# foot-board.net
KiCad netlist of a schematic drawn in EAGLE
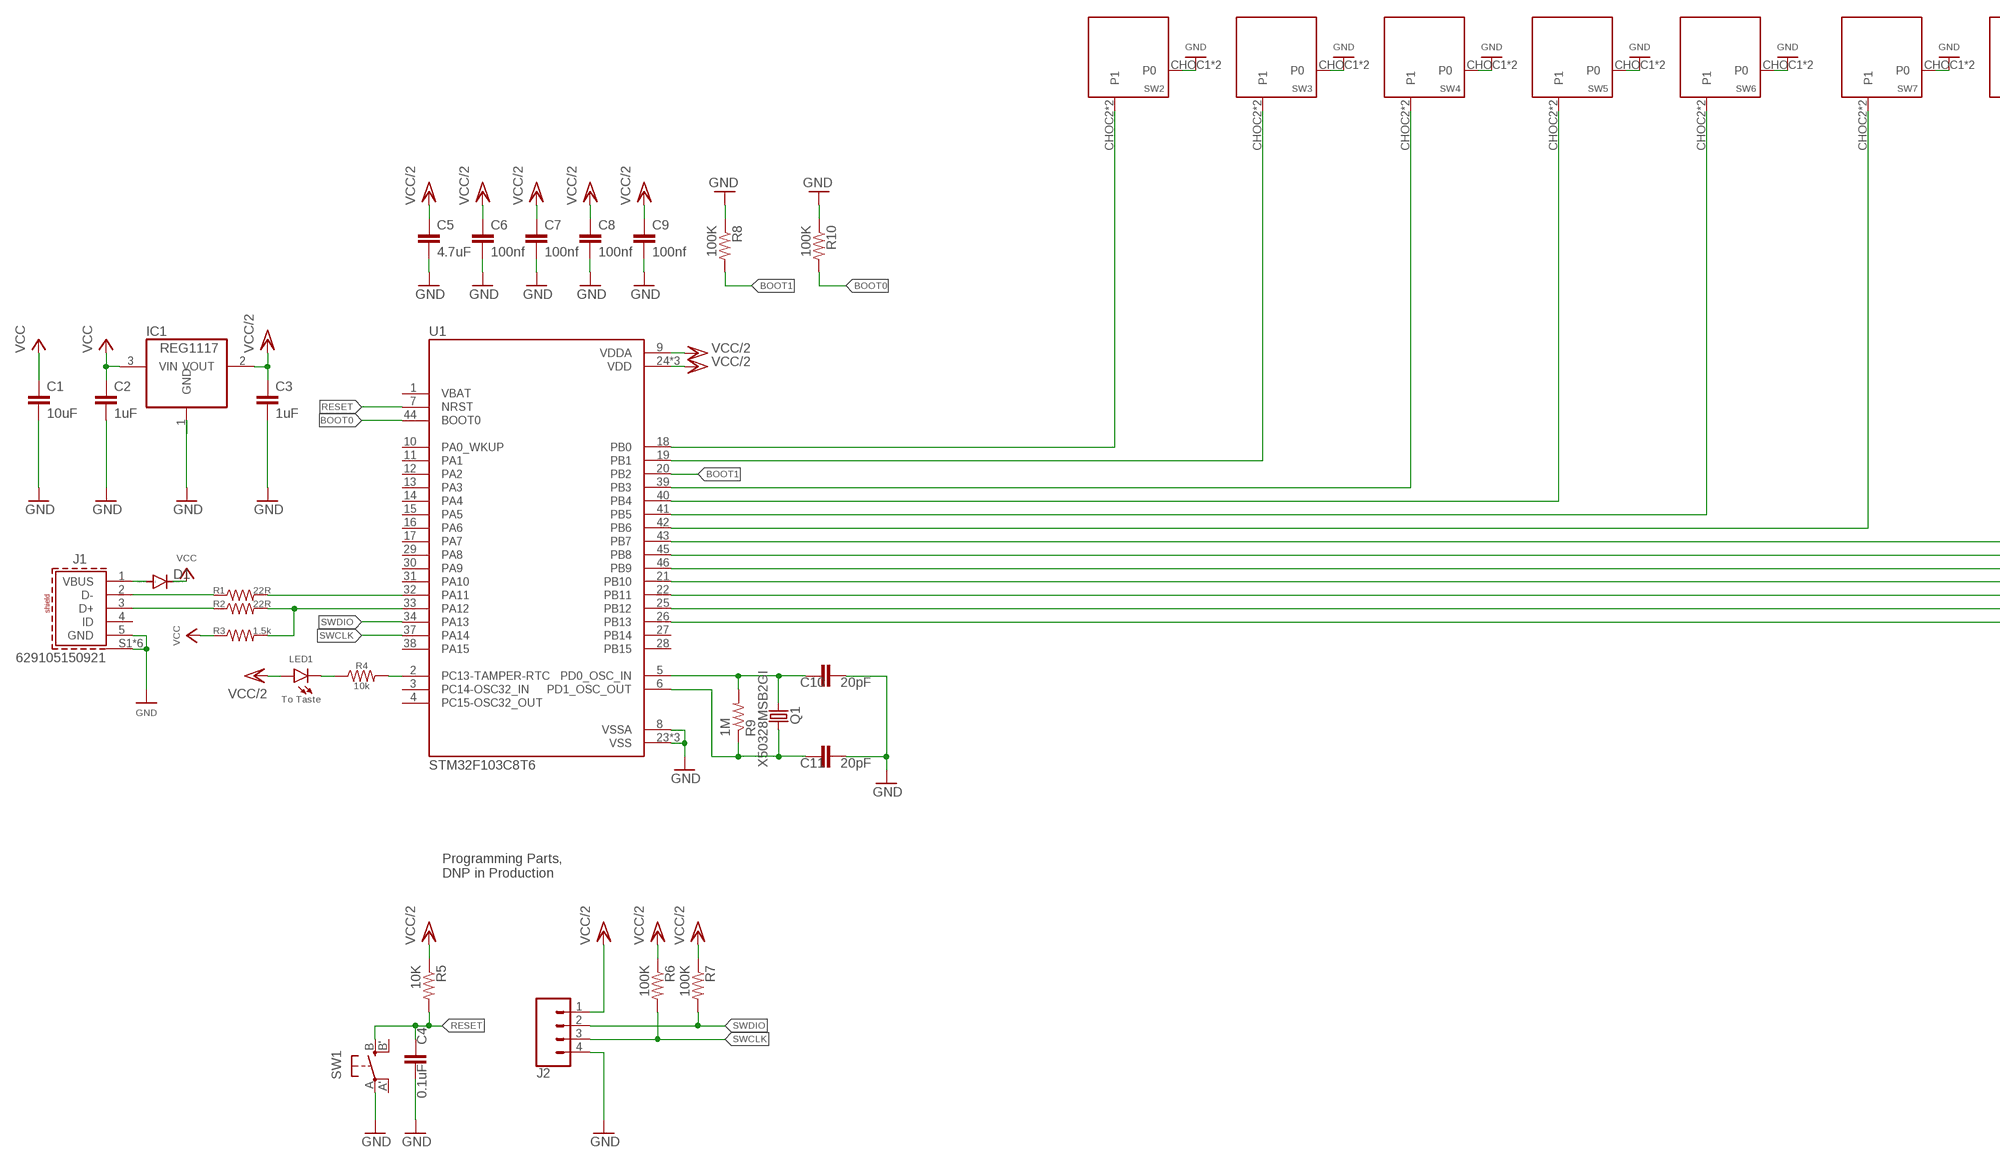
[diagram p0: schematic, sheet 1, part 1 of 2]
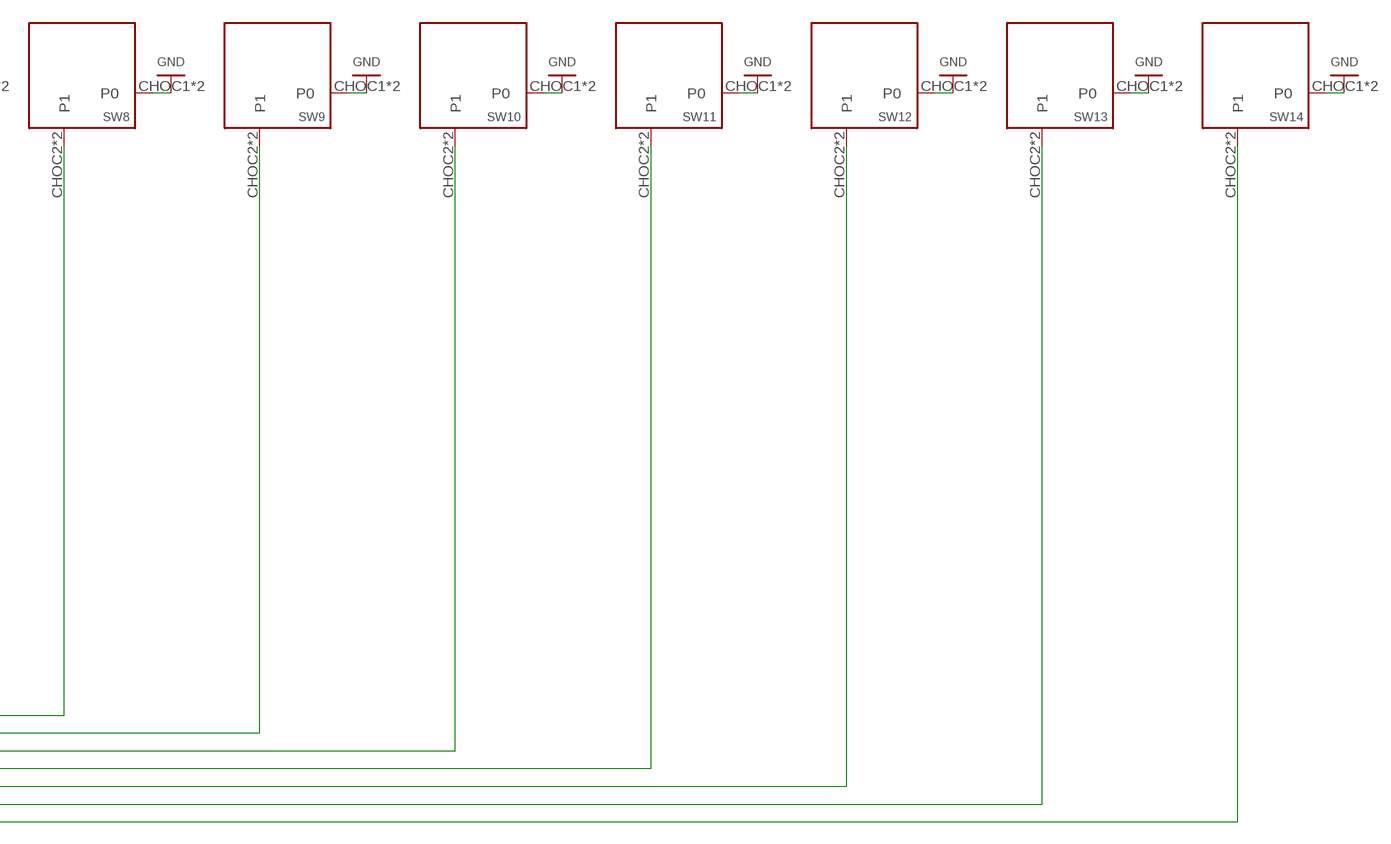
[diagram p1: schematic, sheet 1, part 2 of 2]

(export (version "E")
  (design (tool "Eeschema 10.0.6"))
  (components
    (comp (ref "C1")
      (value "10uF")
      (footprint "eagle-import:C0805")
      (libsource (lib "eagle-import") (part "C-EUC0805"))
    )
    (comp (ref "C2")
      (value "1uF")
      (footprint "eagle-import:C0402")
      (libsource (lib "eagle-import") (part "C-EUC0402"))
    )
    (comp (ref "C3")
      (value "1uF")
      (footprint "eagle-import:C0402")
      (libsource (lib "eagle-import") (part "C-EUC0402"))
    )
    (comp (ref "C4")
      (value "0.1uF")
      (footprint "eagle-import:C0402")
      (libsource (lib "eagle-import") (part "C-EUC0402"))
    )
    (comp (ref "C5")
      (value "4.7uF")
      (footprint "eagle-import:C0805")
      (libsource (lib "eagle-import") (part "C-EUC0805"))
    )
    (comp (ref "C6")
      (value "100nf")
      (footprint "eagle-import:C0402")
      (libsource (lib "eagle-import") (part "C-EUC0402"))
    )
    (comp (ref "C7")
      (value "100nf")
      (footprint "eagle-import:C0402")
      (libsource (lib "eagle-import") (part "C-EUC0402"))
    )
    (comp (ref "C8")
      (value "100nf")
      (footprint "eagle-import:C0402")
      (libsource (lib "eagle-import") (part "C-EUC0402"))
    )
    (comp (ref "C9")
      (value "100nf")
      (footprint "eagle-import:C0402")
      (libsource (lib "eagle-import") (part "C-EUC0402"))
    )
    (comp (ref "C10")
      (value "20pF")
      (footprint "eagle-import:C0402")
      (libsource (lib "eagle-import") (part "C-EUC0402"))
    )
    (comp (ref "C11")
      (value "20pF")
      (footprint "eagle-import:C0402")
      (libsource (lib "eagle-import") (part "C-EUC0402"))
    )
    (comp (ref "D1")
      (value "DIODE-DO214AC")
      (footprint "eagle-import:DO214AC")
      (libsource (lib "eagle-import") (part "DIODE-DO214AC"))
    )
    (comp (ref "IC1")
      (value "REG1117")
      (footprint "eagle-import:SOT223")
      (libsource (lib "eagle-import") (part "REG1117"))
    )
    (comp (ref "J1")
      (value "629105150921")
      (footprint "eagle-import:629105150921")
      (libsource (lib "eagle-import") (part "629105150921"))
    )
    (comp (ref "J2")
      (value "CONN_04")
      (footprint "eagle-import:1X04")
      (libsource (lib "eagle-import") (part "CONN_04"))
    )
    (comp (ref "LED1")
      (value "To Taste")
      (footprint "eagle-import:CHIPLED_0603")
      (libsource (lib "eagle-import") (part "LEDCHIPLED_0603"))
    )
    (comp (ref "Q1")
      (value "X50328MSB2GI")
      (footprint "eagle-import:6.0X3.5_2")
      (libsource (lib "eagle-import") (part "KX-12B"))
    )
    (comp (ref "R1")
      (value "22R")
      (footprint "eagle-import:R0402")
      (libsource (lib "eagle-import") (part "rcl_334_R-US_R0402"))
    )
    (comp (ref "R2")
      (value "22R")
      (footprint "eagle-import:R0402")
      (libsource (lib "eagle-import") (part "rcl_334_R-US_R0402"))
    )
    (comp (ref "R3")
      (value "1.5k")
      (footprint "eagle-import:R0402")
      (libsource (lib "eagle-import") (part "rcl_334_R-US_R0402"))
    )
    (comp (ref "R4")
      (value "10k")
      (footprint "eagle-import:R0402")
      (libsource (lib "eagle-import") (part "rcl_334_R-US_R0402"))
    )
    (comp (ref "R5")
      (value "10K")
      (footprint "eagle-import:R0402")
      (libsource (lib "eagle-import") (part "R-US_R0402"))
    )
    (comp (ref "R6")
      (value "100K")
      (footprint "eagle-import:R0402")
      (libsource (lib "eagle-import") (part "R-US_R0402"))
    )
    (comp (ref "R7")
      (value "100K")
      (footprint "eagle-import:R0402")
      (libsource (lib "eagle-import") (part "R-US_R0402"))
    )
    (comp (ref "R8")
      (value "100K")
      (footprint "eagle-import:R0402")
      (libsource (lib "eagle-import") (part "R-US_R0402"))
    )
    (comp (ref "R9")
      (value "1M")
      (footprint "eagle-import:R0402")
      (libsource (lib "eagle-import") (part "R-US_R0402"))
    )
    (comp (ref "R10")
      (value "100K")
      (footprint "eagle-import:R0402")
      (libsource (lib "eagle-import") (part "R-US_R0402"))
    )
    (comp (ref "SW1")
      (value "SPST_TACT-EVQQ2")
      (footprint "eagle-import:EVQ-Q2")
      (libsource (lib "eagle-import") (part "SPST_TACT-EVQQ2"))
    )
    (comp (ref "SW2")
      (value "KEYSWITCH-PLAIN-CHOCX-1U")
      (footprint "eagle-import:CHOCX-1U")
      (libsource (lib "eagle-import") (part "KEYSWITCH-PLAIN-CHOCX-1U"))
    )
    (comp (ref "SW3")
      (value "KEYSWITCH-PLAIN-CHOCX-1U")
      (footprint "eagle-import:CHOCX-1U")
      (libsource (lib "eagle-import") (part "KEYSWITCH-PLAIN-CHOCX-1U"))
    )
    (comp (ref "SW4")
      (value "KEYSWITCH-PLAIN-CHOCX-1U")
      (footprint "eagle-import:CHOCX-1U")
      (libsource (lib "eagle-import") (part "KEYSWITCH-PLAIN-CHOCX-1U"))
    )
    (comp (ref "SW5")
      (value "KEYSWITCH-PLAIN-CHOCX-1U")
      (footprint "eagle-import:CHOCX-1U")
      (libsource (lib "eagle-import") (part "KEYSWITCH-PLAIN-CHOCX-1U"))
    )
    (comp (ref "SW6")
      (value "KEYSWITCH-PLAIN-CHOCX-1U")
      (footprint "eagle-import:CHOCX-1U")
      (libsource (lib "eagle-import") (part "KEYSWITCH-PLAIN-CHOCX-1U"))
    )
    (comp (ref "SW7")
      (value "KEYSWITCH-PLAIN-CHOCX-1U")
      (footprint "eagle-import:CHOCX-1U")
      (libsource (lib "eagle-import") (part "KEYSWITCH-PLAIN-CHOCX-1U"))
    )
    (comp (ref "SW8")
      (value "KEYSWITCH-PLAIN-CHOCX-1U")
      (footprint "eagle-import:CHOCX-1U")
      (libsource (lib "eagle-import") (part "KEYSWITCH-PLAIN-CHOCX-1U"))
    )
    (comp (ref "SW9")
      (value "KEYSWITCH-PLAIN-CHOCX-1U")
      (footprint "eagle-import:CHOCX-1U")
      (libsource (lib "eagle-import") (part "KEYSWITCH-PLAIN-CHOCX-1U"))
    )
    (comp (ref "SW10")
      (value "KEYSWITCH-PLAIN-CHOCX-1U")
      (footprint "eagle-import:CHOCX-1U")
      (libsource (lib "eagle-import") (part "KEYSWITCH-PLAIN-CHOCX-1U"))
    )
    (comp (ref "SW11")
      (value "KEYSWITCH-PLAIN-CHOCX-1U")
      (footprint "eagle-import:CHOCX-1U")
      (libsource (lib "eagle-import") (part "KEYSWITCH-PLAIN-CHOCX-1U"))
    )
    (comp (ref "SW12")
      (value "KEYSWITCH-PLAIN-CHOCX-1U")
      (footprint "eagle-import:CHOCX-1U")
      (libsource (lib "eagle-import") (part "KEYSWITCH-PLAIN-CHOCX-1U"))
    )
    (comp (ref "SW13")
      (value "KEYSWITCH-PLAIN-CHOCX-1U")
      (footprint "eagle-import:CHOCX-1U")
      (libsource (lib "eagle-import") (part "KEYSWITCH-PLAIN-CHOCX-1U"))
    )
    (comp (ref "SW14")
      (value "KEYSWITCH-PLAIN-CHOCX-1U")
      (footprint "eagle-import:CHOCX-1U")
      (libsource (lib "eagle-import") (part "KEYSWITCH-PLAIN-CHOCX-1U"))
    )
    (comp (ref "U1")
      (value "STM32F103C8T6")
      (footprint "eagle-import:QFP50P900X900X160-48N")
      (fields (field (name "MF") "STMicroelectronics"))
      (libsource (lib "eagle-import") (part "STM32F103C8T6"))
    )
  )
  (nets
    (net (code "1") (name "BOOT0") (class "Default")
      (node (ref "R10") (pin "2") (pinfunction "2_2") (pintype "passive"))
      (node (ref "U1") (pin "44") (pinfunction "BOOT0_44") (pintype "input"))
    )
    (net (code "2") (name "BOOT1") (class "Default")
      (node (ref "R8") (pin "2") (pinfunction "2_2") (pintype "passive"))
      (node (ref "U1") (pin "20") (pinfunction "PB2_20") (pintype "bidirectional"))
    )
    (net (code "3") (name "GND") (class "Default")
      (node (ref "C1") (pin "2") (pinfunction "2_2") (pintype "passive"))
      (node (ref "C10") (pin "2") (pinfunction "2_2") (pintype "passive"))
      (node (ref "C11") (pin "2") (pinfunction "2_2") (pintype "passive"))
      (node (ref "C2") (pin "2") (pinfunction "2_2") (pintype "passive"))
      (node (ref "C3") (pin "2") (pinfunction "2_2") (pintype "passive"))
      (node (ref "C4") (pin "2") (pinfunction "2_2") (pintype "passive"))
      (node (ref "C5") (pin "2") (pinfunction "2_2") (pintype "passive"))
      (node (ref "C6") (pin "2") (pinfunction "2_2") (pintype "passive"))
      (node (ref "C7") (pin "2") (pinfunction "2_2") (pintype "passive"))
      (node (ref "C8") (pin "2") (pinfunction "2_2") (pintype "passive"))
      (node (ref "C9") (pin "2") (pinfunction "2_2") (pintype "passive"))
      (node (ref "IC1") (pin "1") (pinfunction "GND_1") (pintype "power_in"))
      (node (ref "J1") (pin "5") (pinfunction "GND_5") (pintype "passive"))
      (node (ref "J1") (pin "S1") (pinfunction "SHIELD_S1") (pintype "passive"))
      (node (ref "J1") (pin "S2") (pinfunction "SHIELD_S2") (pintype "passive"))
      (node (ref "J1") (pin "S3") (pinfunction "SHIELD_S3") (pintype "passive"))
      (node (ref "J1") (pin "S4") (pinfunction "SHIELD_S4") (pintype "passive"))
      (node (ref "J1") (pin "S5") (pinfunction "SHIELD_S5") (pintype "passive"))
      (node (ref "J1") (pin "S6") (pinfunction "SHIELD_S6") (pintype "passive"))
      (node (ref "J2") (pin "4") (pinfunction "4_4") (pintype "passive"))
      (node (ref "R10") (pin "1") (pinfunction "1_1") (pintype "passive"))
      (node (ref "R8") (pin "1") (pinfunction "1_1") (pintype "passive"))
      (node (ref "SW1") (pin "A") (pinfunction "P_A") (pintype "passive"))
      (node (ref "SW10") (pin "CHOC1") (pinfunction "P0_CHOC1") (pintype "bidirectional"))
      (node (ref "SW10") (pin "X1") (pinfunction "P0_X1") (pintype "bidirectional"))
      (node (ref "SW11") (pin "CHOC1") (pinfunction "P0_CHOC1") (pintype "bidirectional"))
      (node (ref "SW11") (pin "X1") (pinfunction "P0_X1") (pintype "bidirectional"))
      (node (ref "SW12") (pin "CHOC1") (pinfunction "P0_CHOC1") (pintype "bidirectional"))
      (node (ref "SW12") (pin "X1") (pinfunction "P0_X1") (pintype "bidirectional"))
      (node (ref "SW13") (pin "CHOC1") (pinfunction "P0_CHOC1") (pintype "bidirectional"))
      (node (ref "SW13") (pin "X1") (pinfunction "P0_X1") (pintype "bidirectional"))
      (node (ref "SW14") (pin "CHOC1") (pinfunction "P0_CHOC1") (pintype "bidirectional"))
      (node (ref "SW14") (pin "X1") (pinfunction "P0_X1") (pintype "bidirectional"))
      (node (ref "SW2") (pin "CHOC1") (pinfunction "P0_CHOC1") (pintype "bidirectional"))
      (node (ref "SW2") (pin "X1") (pinfunction "P0_X1") (pintype "bidirectional"))
      (node (ref "SW3") (pin "CHOC1") (pinfunction "P0_CHOC1") (pintype "bidirectional"))
      (node (ref "SW3") (pin "X1") (pinfunction "P0_X1") (pintype "bidirectional"))
      (node (ref "SW4") (pin "CHOC1") (pinfunction "P0_CHOC1") (pintype "bidirectional"))
      (node (ref "SW4") (pin "X1") (pinfunction "P0_X1") (pintype "bidirectional"))
      (node (ref "SW5") (pin "CHOC1") (pinfunction "P0_CHOC1") (pintype "bidirectional"))
      (node (ref "SW5") (pin "X1") (pinfunction "P0_X1") (pintype "bidirectional"))
      (node (ref "SW6") (pin "CHOC1") (pinfunction "P0_CHOC1") (pintype "bidirectional"))
      (node (ref "SW6") (pin "X1") (pinfunction "P0_X1") (pintype "bidirectional"))
      (node (ref "SW7") (pin "CHOC1") (pinfunction "P0_CHOC1") (pintype "bidirectional"))
      (node (ref "SW7") (pin "X1") (pinfunction "P0_X1") (pintype "bidirectional"))
      (node (ref "SW8") (pin "CHOC1") (pinfunction "P0_CHOC1") (pintype "bidirectional"))
      (node (ref "SW8") (pin "X1") (pinfunction "P0_X1") (pintype "bidirectional"))
      (node (ref "SW9") (pin "CHOC1") (pinfunction "P0_CHOC1") (pintype "bidirectional"))
      (node (ref "SW9") (pin "X1") (pinfunction "P0_X1") (pintype "bidirectional"))
      (node (ref "U1") (pin "23") (pinfunction "VSS_23") (pintype "power_in"))
      (node (ref "U1") (pin "35") (pinfunction "VSS_35") (pintype "power_in"))
      (node (ref "U1") (pin "47") (pinfunction "VSS_47") (pintype "power_in"))
      (node (ref "U1") (pin "8") (pinfunction "VSSA_8") (pintype "power_in"))
    )
    (net (code "4") (name "Net-(J1-D+)") (class "Default")
      (node (ref "J1") (pin "3") (pinfunction "D+_3") (pintype "passive"))
      (node (ref "R2") (pin "1") (pinfunction "1_1") (pintype "passive"))
    )
    (net (code "5") (name "Net-(J1-D-)") (class "Default")
      (node (ref "J1") (pin "2") (pinfunction "D-_2") (pintype "passive"))
      (node (ref "R1") (pin "1") (pinfunction "1_1") (pintype "passive"))
    )
    (net (code "6") (name "Net-(J1-VBUS)") (class "Default")
      (node (ref "D1") (pin "A") (pinfunction "A_A") (pintype "passive"))
      (node (ref "J1") (pin "1") (pinfunction "VBUS_1") (pintype "passive"))
    )
    (net (code "7") (name "Net-(LED1-PadC)") (class "Default")
      (node (ref "LED1") (pin "C") (pinfunction "C_C") (pintype "passive"))
      (node (ref "R4") (pin "1") (pinfunction "1_1") (pintype "passive"))
    )
    (net (code "8") (name "Net-(U1-PA11)") (class "Default")
      (node (ref "R1") (pin "2") (pinfunction "2_2") (pintype "passive"))
      (node (ref "U1") (pin "32") (pinfunction "PA11_32") (pintype "bidirectional"))
    )
    (net (code "9") (name "Net-(U1-PA12)") (class "Default")
      (node (ref "R2") (pin "2") (pinfunction "2_2") (pintype "passive"))
      (node (ref "R3") (pin "2") (pinfunction "2_2") (pintype "passive"))
      (node (ref "U1") (pin "33") (pinfunction "PA12_33") (pintype "bidirectional"))
    )
    (net (code "10") (name "Net-(U1-PB0)") (class "Default")
      (node (ref "SW2") (pin "CHOC2") (pinfunction "P1_CHOC2") (pintype "bidirectional"))
      (node (ref "SW2") (pin "X2") (pinfunction "P1_X2") (pintype "bidirectional"))
      (node (ref "U1") (pin "18") (pinfunction "PB0_18") (pintype "bidirectional"))
    )
    (net (code "11") (name "Net-(U1-PB1)") (class "Default")
      (node (ref "SW3") (pin "CHOC2") (pinfunction "P1_CHOC2") (pintype "bidirectional"))
      (node (ref "SW3") (pin "X2") (pinfunction "P1_X2") (pintype "bidirectional"))
      (node (ref "U1") (pin "19") (pinfunction "PB1_19") (pintype "bidirectional"))
    )
    (net (code "12") (name "Net-(U1-PB3)") (class "Default")
      (node (ref "SW4") (pin "CHOC2") (pinfunction "P1_CHOC2") (pintype "bidirectional"))
      (node (ref "SW4") (pin "X2") (pinfunction "P1_X2") (pintype "bidirectional"))
      (node (ref "U1") (pin "39") (pinfunction "PB3_39") (pintype "bidirectional"))
    )
    (net (code "13") (name "Net-(U1-PB4)") (class "Default")
      (node (ref "SW5") (pin "CHOC2") (pinfunction "P1_CHOC2") (pintype "bidirectional"))
      (node (ref "SW5") (pin "X2") (pinfunction "P1_X2") (pintype "bidirectional"))
      (node (ref "U1") (pin "40") (pinfunction "PB4_40") (pintype "bidirectional"))
    )
    (net (code "14") (name "Net-(U1-PB5)") (class "Default")
      (node (ref "SW6") (pin "CHOC2") (pinfunction "P1_CHOC2") (pintype "bidirectional"))
      (node (ref "SW6") (pin "X2") (pinfunction "P1_X2") (pintype "bidirectional"))
      (node (ref "U1") (pin "41") (pinfunction "PB5_41") (pintype "bidirectional"))
    )
    (net (code "15") (name "Net-(U1-PB6)") (class "Default")
      (node (ref "SW7") (pin "CHOC2") (pinfunction "P1_CHOC2") (pintype "bidirectional"))
      (node (ref "SW7") (pin "X2") (pinfunction "P1_X2") (pintype "bidirectional"))
      (node (ref "U1") (pin "42") (pinfunction "PB6_42") (pintype "bidirectional"))
    )
    (net (code "16") (name "Net-(U1-PB7)") (class "Default")
      (node (ref "SW8") (pin "CHOC2") (pinfunction "P1_CHOC2") (pintype "bidirectional"))
      (node (ref "SW8") (pin "X2") (pinfunction "P1_X2") (pintype "bidirectional"))
      (node (ref "U1") (pin "43") (pinfunction "PB7_43") (pintype "bidirectional"))
    )
    (net (code "17") (name "Net-(U1-PB8)") (class "Default")
      (node (ref "SW9") (pin "CHOC2") (pinfunction "P1_CHOC2") (pintype "bidirectional"))
      (node (ref "SW9") (pin "X2") (pinfunction "P1_X2") (pintype "bidirectional"))
      (node (ref "U1") (pin "45") (pinfunction "PB8_45") (pintype "bidirectional"))
    )
    (net (code "18") (name "Net-(U1-PB9)") (class "Default")
      (node (ref "SW10") (pin "CHOC2") (pinfunction "P1_CHOC2") (pintype "bidirectional"))
      (node (ref "SW10") (pin "X2") (pinfunction "P1_X2") (pintype "bidirectional"))
      (node (ref "U1") (pin "46") (pinfunction "PB9_46") (pintype "bidirectional"))
    )
    (net (code "19") (name "Net-(U1-PB10)") (class "Default")
      (node (ref "SW11") (pin "CHOC2") (pinfunction "P1_CHOC2") (pintype "bidirectional"))
      (node (ref "SW11") (pin "X2") (pinfunction "P1_X2") (pintype "bidirectional"))
      (node (ref "U1") (pin "21") (pinfunction "PB10_21") (pintype "bidirectional"))
    )
    (net (code "20") (name "Net-(U1-PB11)") (class "Default")
      (node (ref "SW12") (pin "CHOC2") (pinfunction "P1_CHOC2") (pintype "bidirectional"))
      (node (ref "SW12") (pin "X2") (pinfunction "P1_X2") (pintype "bidirectional"))
      (node (ref "U1") (pin "22") (pinfunction "PB11_22") (pintype "bidirectional"))
    )
    (net (code "21") (name "Net-(U1-PB12)") (class "Default")
      (node (ref "SW13") (pin "CHOC2") (pinfunction "P1_CHOC2") (pintype "bidirectional"))
      (node (ref "SW13") (pin "X2") (pinfunction "P1_X2") (pintype "bidirectional"))
      (node (ref "U1") (pin "25") (pinfunction "PB12_25") (pintype "bidirectional"))
    )
    (net (code "22") (name "Net-(U1-PB13)") (class "Default")
      (node (ref "SW14") (pin "CHOC2") (pinfunction "P1_CHOC2") (pintype "bidirectional"))
      (node (ref "SW14") (pin "X2") (pinfunction "P1_X2") (pintype "bidirectional"))
      (node (ref "U1") (pin "26") (pinfunction "PB13_26") (pintype "bidirectional"))
    )
    (net (code "23") (name "Net-(U1-PC13-TAMPER-RTC)") (class "Default")
      (node (ref "R4") (pin "2") (pinfunction "2_2") (pintype "passive"))
      (node (ref "U1") (pin "2") (pinfunction "PC13-TAMPER-RTC_2") (pintype "bidirectional"))
    )
    (net (code "24") (name "Net-(U1-PD0_OSC_IN)") (class "Default")
      (node (ref "C10") (pin "1") (pinfunction "1_1") (pintype "passive"))
      (node (ref "Q1") (pin "2") (pinfunction "2_2") (pintype "passive"))
      (node (ref "R9") (pin "2") (pinfunction "2_2") (pintype "passive"))
      (node (ref "U1") (pin "5") (pinfunction "PD0_OSC_IN_5") (pintype "bidirectional"))
    )
    (net (code "25") (name "Net-(U1-PD1_OSC_OUT)") (class "Default")
      (node (ref "C11") (pin "1") (pinfunction "1_1") (pintype "passive"))
      (node (ref "Q1") (pin "1") (pinfunction "1_1") (pintype "passive"))
      (node (ref "R9") (pin "1") (pinfunction "1_1") (pintype "passive"))
      (node (ref "U1") (pin "6") (pinfunction "PD1_OSC_OUT_6") (pintype "bidirectional"))
    )
    (net (code "26") (name "RESET") (class "Default")
      (node (ref "C4") (pin "1") (pinfunction "1_1") (pintype "passive"))
      (node (ref "R5") (pin "2") (pinfunction "2_2") (pintype "passive"))
      (node (ref "SW1") (pin "B") (pinfunction "S_B") (pintype "passive"))
      (node (ref "U1") (pin "7") (pinfunction "NRST_7") (pintype "input"))
    )
    (net (code "27") (name "SWCLK") (class "Default")
      (node (ref "J2") (pin "3") (pinfunction "3_3") (pintype "passive"))
      (node (ref "R6") (pin "2") (pinfunction "2_2") (pintype "passive"))
      (node (ref "U1") (pin "37") (pinfunction "PA14_37") (pintype "bidirectional"))
    )
    (net (code "28") (name "SWDIO") (class "Default")
      (node (ref "J2") (pin "2") (pinfunction "2_2") (pintype "passive"))
      (node (ref "R7") (pin "2") (pinfunction "2_2") (pintype "passive"))
      (node (ref "U1") (pin "34") (pinfunction "PA13_34") (pintype "bidirectional"))
    )
    (net (code "29") (name "VCC") (class "Default")
      (node (ref "C1") (pin "1") (pinfunction "1_1") (pintype "passive"))
      (node (ref "C2") (pin "1") (pinfunction "1_1") (pintype "passive"))
      (node (ref "D1") (pin "C") (pinfunction "C_C") (pintype "passive"))
      (node (ref "IC1") (pin "3") (pinfunction "VIN_3") (pintype "input"))
      (node (ref "R3") (pin "1") (pinfunction "1_1") (pintype "passive"))
    )
    (net (code "30") (name "VCC{slash}2") (class "Default")
      (node (ref "C3") (pin "1") (pinfunction "1_1") (pintype "passive"))
      (node (ref "C5") (pin "1") (pinfunction "1_1") (pintype "passive"))
      (node (ref "C6") (pin "1") (pinfunction "1_1") (pintype "passive"))
      (node (ref "C7") (pin "1") (pinfunction "1_1") (pintype "passive"))
      (node (ref "C8") (pin "1") (pinfunction "1_1") (pintype "passive"))
      (node (ref "C9") (pin "1") (pinfunction "1_1") (pintype "passive"))
      (node (ref "IC1") (pin "2") (pinfunction "VOUT_2") (pintype "output"))
      (node (ref "J2") (pin "1") (pinfunction "1_1") (pintype "passive"))
      (node (ref "LED1") (pin "A") (pinfunction "A_A") (pintype "passive"))
      (node (ref "R5") (pin "1") (pinfunction "1_1") (pintype "passive"))
      (node (ref "R6") (pin "1") (pinfunction "1_1") (pintype "passive"))
      (node (ref "R7") (pin "1") (pinfunction "1_1") (pintype "passive"))
      (node (ref "U1") (pin "24") (pinfunction "VDD_24") (pintype "power_in"))
      (node (ref "U1") (pin "36") (pinfunction "VDD_36") (pintype "power_in"))
      (node (ref "U1") (pin "48") (pinfunction "VDD_48") (pintype "power_in"))
      (node (ref "U1") (pin "9") (pinfunction "VDDA_9") (pintype "power_in"))
    )
    (net (code "31") (name "unconnected-(J1-ID-Pad4)") (class "Default")
      (node (ref "J1") (pin "4") (pinfunction "ID_4") (pintype "passive"))
    )
    (net (code "32") (name "unconnected-(SW1-P1-PadA')") (class "Default")
      (node (ref "SW1") (pin "A'") (pinfunction "P1_A'") (pintype "passive"))
    )
    (net (code "33") (name "unconnected-(SW1-S1-PadB')") (class "Default")
      (node (ref "SW1") (pin "B'") (pinfunction "S1_B'") (pintype "passive"))
    )
    (net (code "34") (name "unconnected-(U1-PA0_WKUP-Pad10)") (class "Default")
      (node (ref "U1") (pin "10") (pinfunction "PA0_WKUP_10") (pintype "bidirectional"))
    )
    (net (code "35") (name "unconnected-(U1-PA1-Pad11)") (class "Default")
      (node (ref "U1") (pin "11") (pinfunction "PA1_11") (pintype "bidirectional"))
    )
    (net (code "36") (name "unconnected-(U1-PA2-Pad12)") (class "Default")
      (node (ref "U1") (pin "12") (pinfunction "PA2_12") (pintype "bidirectional"))
    )
    (net (code "37") (name "unconnected-(U1-PA3-Pad13)") (class "Default")
      (node (ref "U1") (pin "13") (pinfunction "PA3_13") (pintype "bidirectional"))
    )
    (net (code "38") (name "unconnected-(U1-PA4-Pad14)") (class "Default")
      (node (ref "U1") (pin "14") (pinfunction "PA4_14") (pintype "bidirectional"))
    )
    (net (code "39") (name "unconnected-(U1-PA5-Pad15)") (class "Default")
      (node (ref "U1") (pin "15") (pinfunction "PA5_15") (pintype "bidirectional"))
    )
    (net (code "40") (name "unconnected-(U1-PA6-Pad16)") (class "Default")
      (node (ref "U1") (pin "16") (pinfunction "PA6_16") (pintype "bidirectional"))
    )
    (net (code "41") (name "unconnected-(U1-PA7-Pad17)") (class "Default")
      (node (ref "U1") (pin "17") (pinfunction "PA7_17") (pintype "bidirectional"))
    )
    (net (code "42") (name "unconnected-(U1-PA8-Pad29)") (class "Default")
      (node (ref "U1") (pin "29") (pinfunction "PA8_29") (pintype "bidirectional"))
    )
    (net (code "43") (name "unconnected-(U1-PA9-Pad30)") (class "Default")
      (node (ref "U1") (pin "30") (pinfunction "PA9_30") (pintype "bidirectional"))
    )
    (net (code "44") (name "unconnected-(U1-PA10-Pad31)") (class "Default")
      (node (ref "U1") (pin "31") (pinfunction "PA10_31") (pintype "bidirectional"))
    )
    (net (code "45") (name "unconnected-(U1-PA15-Pad38)") (class "Default")
      (node (ref "U1") (pin "38") (pinfunction "PA15_38") (pintype "bidirectional"))
    )
    (net (code "46") (name "unconnected-(U1-PB14-Pad27)") (class "Default")
      (node (ref "U1") (pin "27") (pinfunction "PB14_27") (pintype "bidirectional"))
    )
    (net (code "47") (name "unconnected-(U1-PB15-Pad28)") (class "Default")
      (node (ref "U1") (pin "28") (pinfunction "PB15_28") (pintype "bidirectional"))
    )
    (net (code "48") (name "unconnected-(U1-PC14-OSC32_IN-Pad3)") (class "Default")
      (node (ref "U1") (pin "3") (pinfunction "PC14-OSC32_IN_3") (pintype "bidirectional"))
    )
    (net (code "49") (name "unconnected-(U1-PC15-OSC32_OUT-Pad4)") (class "Default")
      (node (ref "U1") (pin "4") (pinfunction "PC15-OSC32_OUT_4") (pintype "bidirectional"))
    )
    (net (code "50") (name "unconnected-(U1-VBAT-Pad1)") (class "Default")
      (node (ref "U1") (pin "1") (pinfunction "VBAT_1") (pintype "bidirectional"))
    )
  )
)
